# Sheet1.net
KiCad netlist of a schematic drawn in Altium Designer
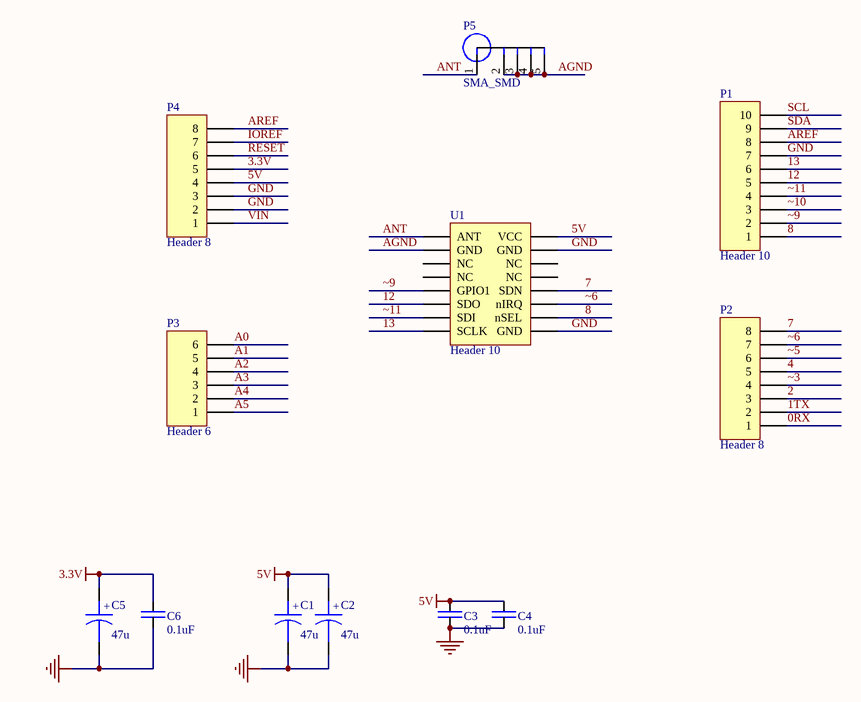
[diagram p0: Sheet1.SchDoc]

(export (version "E")
  (design (tool "Eeschema 10.0.6"))
  (components
    (comp (ref "C1")
      (value "47u")
      (footprint "3216C")
      (description "Capacitor")
      (libsource (lib "*") (part "CAPACITOR POL"))
    )
    (comp (ref "C2")
      (value "47u")
      (footprint "3216C")
      (description "Capacitor")
      (libsource (lib "*") (part "CAPACITOR POL"))
    )
    (comp (ref "C3")
      (value "0.1uF")
      (footprint "0603")
      (description "Capacitor")
      (libsource (lib "*") (part "CAP"))
    )
    (comp (ref "C4")
      (value "0.1uF")
      (footprint "0603")
      (description "Capacitor")
      (libsource (lib "*") (part "CAP"))
    )
    (comp (ref "C5")
      (value "47u")
      (footprint "3216C")
      (description "Capacitor")
      (libsource (lib "*") (part "CAPACITOR POL"))
    )
    (comp (ref "C6")
      (value "0.1uF")
      (footprint "0603")
      (description "Capacitor")
      (libsource (lib "*") (part "CAP"))
    )
    (comp (ref "P1")
      (value "Header 10")
      (footprint "HDR1X10")
      (description "Header, 10-Pin")
      (fields (field (name "PUBLISHER") "Altium Limited"))
      (libsource (lib "Miscellaneous Connectors") (part "Header 10"))
    )
    (comp (ref "P2")
      (value "Header 8")
      (footprint "HDR1X8")
      (description "Header, 8-Pin")
      (fields (field (name "PUBLISHER") "Altium Limited"))
      (libsource (lib "Miscellaneous Connectors") (part "Header 8"))
    )
    (comp (ref "P3")
      (value "Header 6")
      (footprint "HDR1X6")
      (description "Header, 6-Pin")
      (fields (field (name "PUBLISHER") "Altium Limited"))
      (libsource (lib "Miscellaneous Connectors") (part "Header 6"))
    )
    (comp (ref "P4")
      (value "Header 8")
      (footprint "HDR1X8")
      (description "Header, 8-Pin")
      (fields (field (name "PUBLISHER") "Altium Limited"))
      (libsource (lib "Miscellaneous Connectors") (part "Header 8"))
    )
    (comp (ref "P5") (value "SMA_SMD") (footprint "SMA") (libsource (lib "PCB_Project1") (part "SMA_SMD")))
    (comp (ref "U1")
      (value "Header 10")
      (footprint "RF4463F30")
      (description "Header, 10-Pin")
      (fields (field (name "PUBLISHER") "Altium Limited"))
      (libsource (lib "PCB_Project1") (part "RF4463F30"))
    )
  )
  (nets
    (net (code "1") (name "/0RX") (class "Default")
      (node (ref "P2") (pin "1") (pinfunction "1_1") (pintype "passive"))
    )
    (net (code "2") (name "/1TX") (class "Default")
      (node (ref "P2") (pin "2") (pinfunction "2_2") (pintype "passive"))
    )
    (net (code "3") (name "/2") (class "Default")
      (node (ref "P2") (pin "3") (pinfunction "3_3") (pintype "passive"))
    )
    (net (code "4") (name "/4") (class "Default")
      (node (ref "P2") (pin "5") (pinfunction "5_5") (pintype "passive"))
    )
    (net (code "5") (name "/7") (class "Default")
      (node (ref "P2") (pin "8") (pinfunction "8_8") (pintype "passive"))
      (node (ref "U1") (pin "5") (pinfunction "SDN_5") (pintype "passive"))
    )
    (net (code "6") (name "/8") (class "Default")
      (node (ref "P1") (pin "1") (pinfunction "1_1") (pintype "passive"))
      (node (ref "U1") (pin "7") (pinfunction "nSEL_7") (pintype "passive"))
    )
    (net (code "7") (name "/12") (class "Default")
      (node (ref "P1") (pin "5") (pinfunction "5_5") (pintype "passive"))
      (node (ref "U1") (pin "11") (pinfunction "SDO_11") (pintype "passive"))
    )
    (net (code "8") (name "/13") (class "Default")
      (node (ref "P1") (pin "6") (pinfunction "6_6") (pintype "passive"))
      (node (ref "U1") (pin "9") (pinfunction "SCLK_9") (pintype "passive"))
    )
    (net (code "9") (name "/A0") (class "Default")
      (node (ref "P3") (pin "6") (pinfunction "6_6") (pintype "passive"))
    )
    (net (code "10") (name "/A1") (class "Default")
      (node (ref "P3") (pin "5") (pinfunction "5_5") (pintype "passive"))
    )
    (net (code "11") (name "/A2") (class "Default")
      (node (ref "P3") (pin "4") (pinfunction "4_4") (pintype "passive"))
    )
    (net (code "12") (name "/A3") (class "Default")
      (node (ref "P3") (pin "3") (pinfunction "3_3") (pintype "passive"))
    )
    (net (code "13") (name "/A4") (class "Default")
      (node (ref "P3") (pin "2") (pinfunction "2_2") (pintype "passive"))
    )
    (net (code "14") (name "/A5") (class "Default")
      (node (ref "P3") (pin "1") (pinfunction "1_1") (pintype "passive"))
    )
    (net (code "15") (name "/AGND") (class "Default")
      (node (ref "P5") (pin "2") (pinfunction "2_2") (pintype "passive"))
      (node (ref "P5") (pin "3") (pinfunction "3_3") (pintype "passive"))
      (node (ref "P5") (pin "4") (pinfunction "4_4") (pintype "passive"))
      (node (ref "P5") (pin "5") (pinfunction "5_5") (pintype "passive"))
      (node (ref "U1") (pin "15") (pinfunction "GND_15") (pintype "passive"))
    )
    (net (code "16") (name "/ANT") (class "Default")
      (node (ref "P5") (pin "1") (pinfunction "1_1") (pintype "passive"))
      (node (ref "U1") (pin "16") (pinfunction "ANT_16") (pintype "passive"))
    )
    (net (code "17") (name "/AREF") (class "Default")
      (node (ref "P1") (pin "8") (pinfunction "8_8") (pintype "passive"))
      (node (ref "P4") (pin "8") (pinfunction "8_8") (pintype "passive"))
    )
    (net (code "18") (name "/IOREF") (class "Default")
      (node (ref "P4") (pin "7") (pinfunction "7_7") (pintype "passive"))
    )
    (net (code "19") (name "/RESET") (class "Default")
      (node (ref "P4") (pin "6") (pinfunction "6_6") (pintype "passive"))
    )
    (net (code "20") (name "/SCL") (class "Default")
      (node (ref "P1") (pin "10") (pinfunction "10_10") (pintype "passive"))
    )
    (net (code "21") (name "/SDA") (class "Default")
      (node (ref "P1") (pin "9") (pinfunction "9_9") (pintype "passive"))
    )
    (net (code "22") (name "/VIN") (class "Default")
      (node (ref "P4") (pin "1") (pinfunction "1_1") (pintype "passive"))
    )
    (net (code "23") (name "/~3") (class "Default")
      (node (ref "P2") (pin "4") (pinfunction "4_4") (pintype "passive"))
    )
    (net (code "24") (name "/~5") (class "Default")
      (node (ref "P2") (pin "6") (pinfunction "6_6") (pintype "passive"))
    )
    (net (code "25") (name "/~6") (class "Default")
      (node (ref "P2") (pin "7") (pinfunction "7_7") (pintype "passive"))
      (node (ref "U1") (pin "6") (pinfunction "nIRQ_6") (pintype "passive"))
    )
    (net (code "26") (name "/~9") (class "Default")
      (node (ref "P1") (pin "2") (pinfunction "2_2") (pintype "passive"))
      (node (ref "U1") (pin "12") (pinfunction "GPIO1_12") (pintype "passive"))
    )
    (net (code "27") (name "/~10") (class "Default")
      (node (ref "P1") (pin "3") (pinfunction "3_3") (pintype "passive"))
    )
    (net (code "28") (name "/~11") (class "Default")
      (node (ref "P1") (pin "4") (pinfunction "4_4") (pintype "passive"))
      (node (ref "U1") (pin "10") (pinfunction "SDI_10") (pintype "passive"))
    )
    (net (code "29") (name "3.3V") (class "Default")
      (node (ref "C5") (pin "1") (pinfunction "1_1") (pintype "passive"))
      (node (ref "C6") (pin "1") (pinfunction "1_1") (pintype "passive"))
      (node (ref "P4") (pin "5") (pinfunction "5_5") (pintype "passive"))
    )
    (net (code "30") (name "5V") (class "Default")
      (node (ref "C1") (pin "1") (pinfunction "1_1") (pintype "passive"))
      (node (ref "C2") (pin "1") (pinfunction "1_1") (pintype "passive"))
      (node (ref "C3") (pin "1") (pinfunction "1_1") (pintype "passive"))
      (node (ref "C4") (pin "1") (pinfunction "1_1") (pintype "passive"))
      (node (ref "P4") (pin "4") (pinfunction "4_4") (pintype "passive"))
      (node (ref "U1") (pin "1") (pinfunction "VCC_1") (pintype "passive"))
    )
    (net (code "31") (name "GND") (class "Default")
      (node (ref "C1") (pin "2") (pinfunction "2_2") (pintype "passive"))
      (node (ref "C2") (pin "2") (pinfunction "2_2") (pintype "passive"))
      (node (ref "C3") (pin "2") (pinfunction "2_2") (pintype "passive"))
      (node (ref "C4") (pin "2") (pinfunction "2_2") (pintype "passive"))
      (node (ref "C5") (pin "2") (pinfunction "2_2") (pintype "passive"))
      (node (ref "C6") (pin "2") (pinfunction "2_2") (pintype "passive"))
      (node (ref "P1") (pin "7") (pinfunction "7_7") (pintype "passive"))
      (node (ref "P4") (pin "2") (pinfunction "2_2") (pintype "passive"))
      (node (ref "P4") (pin "3") (pinfunction "3_3") (pintype "passive"))
      (node (ref "U1") (pin "2") (pinfunction "GND_2") (pintype "passive"))
      (node (ref "U1") (pin "8") (pinfunction "GND_8") (pintype "passive"))
    )
    (net (code "32") (name "unconnected-(U1-NC-Pad3)") (class "Default")
      (node (ref "U1") (pin "3") (pinfunction "NC_3") (pintype "passive"))
    )
    (net (code "33") (name "unconnected-(U1-NC-Pad4)") (class "Default")
      (node (ref "U1") (pin "4") (pinfunction "NC_4") (pintype "passive"))
    )
    (net (code "34") (name "unconnected-(U1-NC-Pad13)") (class "Default")
      (node (ref "U1") (pin "13") (pinfunction "NC_13") (pintype "passive"))
    )
    (net (code "35") (name "unconnected-(U1-NC-Pad14)") (class "Default")
      (node (ref "U1") (pin "14") (pinfunction "NC_14") (pintype "passive"))
    )
  )
)
